# I2C_Keypad.net
KiCad netlist of a schematic drawn in Altium Designer
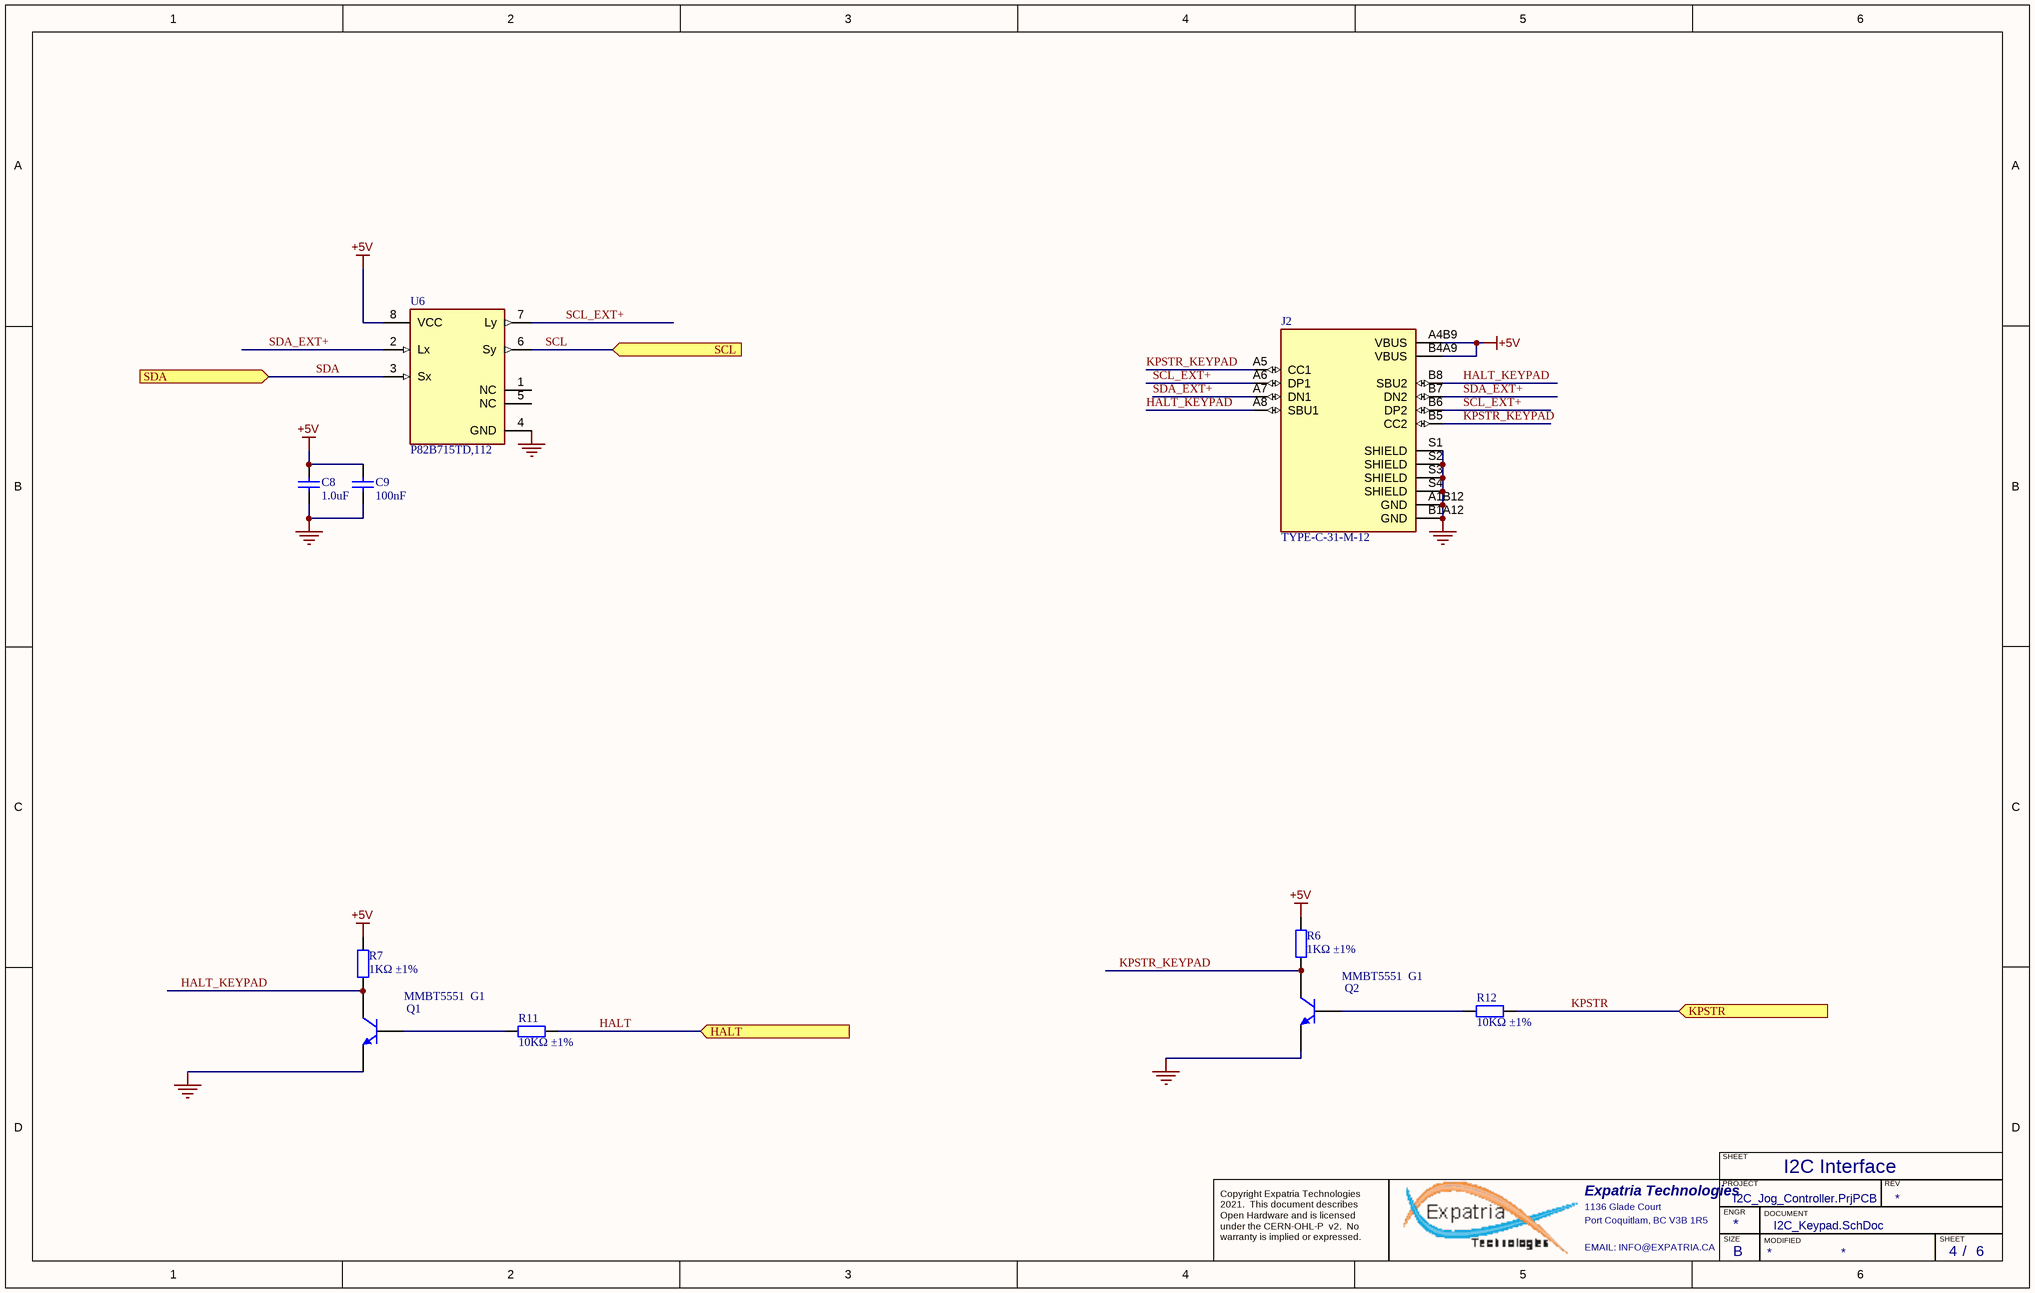
[diagram p0: I2C_Keypad.SchDoc]

(export (version "E")
  (design (tool "Eeschema 10.0.6"))
  (components
    (comp (ref "C8")
      (value "1.0uF")
      (footprint "0402_C")
      (description "Chip capacitor")
      (fields
        (field (name "MANUFACTURER") "Samsung Electro-Mechanics")
        (field (name "PARTNUMBER") "CL05A105KA5NQNC")
      )
      (libsource (lib "Cap") (part "0402 1.0uF (105) 10% 25V"))
    )
    (comp (ref "C9")
      (value "100nF")
      (footprint "0402_C")
      (description "Chip capacitors")
      (fields
        (field (name "MANUFACTURER") "Samsung Electro-Mechanics")
        (field (name "PARTNUMBER") "CL05B104KO5NNNC")
      )
      (libsource (lib "Cap") (part "0402 100nF (104) 10% 16V"))
    )
    (comp (ref "J2")
      (value "TYPE-C-31-M-12")
      (footprint "HRO_TYPE-C-31-M-12")
      (description "USB Connectors 24 Receptacle 1 8.94*7.3mm RoHS")
      (fields (field (name "MF") "HRO Electronics Co., Ltd."))
      (libsource (lib "Universal_CNC_Breakout") (part "TYPE-C-31-M-12"))
    )
    (comp (ref "Q1")
      (value "MMBT5551  G1")
      (footprint "SOT-23(SOT-23-3)")
      (description "三极管")
      (libsource (lib "Transistor_NPN") (part "SOT-23 MMBT5551  G1"))
    )
    (comp (ref "Q2")
      (value "MMBT5551  G1")
      (footprint "SOT-23(SOT-23-3)")
      (description "三极管")
      (libsource (lib "Transistor_NPN") (part "SOT-23 MMBT5551  G1"))
    )
    (comp (ref "R6")
      (value "1KΩ ±1%")
      (footprint "0402_R")
      (description "Chip resistor")
      (fields (field (name "MANUFACTURER") "Uniroyal Elec") (field (name "PARTNUMBER") "0402WGF1001TCE"))
      (libsource (lib "RES") (part "0402 1K (1001) 1%"))
    )
    (comp (ref "R7")
      (value "1KΩ ±1%")
      (footprint "0402_R")
      (description "Chip resistor")
      (fields (field (name "MANUFACTURER") "Uniroyal Elec") (field (name "PARTNUMBER") "0402WGF1001TCE"))
      (libsource (lib "RES") (part "0402 1K (1001) 1%"))
    )
    (comp (ref "R11")
      (value "10KΩ ±1%")
      (footprint "0402_R")
      (description "Chip resistor")
      (fields (field (name "MANUFACTURER") "Uniroyal Elec") (field (name "PARTNUMBER") "0402WGF1002TCE"))
      (libsource (lib "") (part "0402 10K (1002) 1%_1"))
    )
    (comp (ref "R12")
      (value "10KΩ ±1%")
      (footprint "0402_R")
      (description "Chip resistor")
      (fields (field (name "MANUFACTURER") "Uniroyal Elec") (field (name "PARTNUMBER") "0402WGF1002TCE"))
      (libsource (lib "RES") (part "0402 10K (1002) 1%"))
    )
    (comp (ref "U6")
      (value "P82B715TD,112")
      (footprint "FP-SOT96-1-MFG")
      (description "IC REDRIVER I2C 1CH 400KHZ 8SO")
      (fields
        (field (name "MANUFACTURER") "NXP Semicon")
        (field (name "MANUFACTURER_PART_NUMBER") "P82B715TD,118")
      )
      (libsource (lib "Altium Content Vault") (part "feec727f4072afc4f94d4e12e138974"))
    )
  )
  (nets
    (net (code "1") (name "+5V") (class "Default")
      (node (ref "C8") (pin "2") (pinfunction "2_2") (pintype "passive"))
      (node (ref "C9") (pin "2") (pinfunction "2_2") (pintype "passive"))
      (node (ref "J2") (pin "A4B9") (pinfunction "VBUS_A4B9") (pintype "power_in"))
      (node (ref "J2") (pin "B4A9") (pinfunction "VBUS_B4A9") (pintype "power_in"))
      (node (ref "R6") (pin "1") (pinfunction "1_1") (pintype "passive"))
      (node (ref "R7") (pin "1") (pinfunction "1_1") (pintype "passive"))
      (node (ref "U6") (pin "8") (pinfunction "VCC_8") (pintype "power_in"))
    )
    (net (code "2") (name "/HALT") (class "Default")
      (node (ref "R11") (pin "2") (pinfunction "2_2") (pintype "passive"))
    )
    (net (code "3") (name "/HALT_KEYPAD") (class "Default")
      (node (ref "J2") (pin "A8") (pinfunction "SBU1_A8") (pintype "bidirectional"))
      (node (ref "J2") (pin "B8") (pinfunction "SBU2_B8") (pintype "bidirectional"))
      (node (ref "Q1") (pin "3") (pinfunction "C_3") (pintype "passive"))
      (node (ref "R7") (pin "2") (pinfunction "2_2") (pintype "passive"))
    )
    (net (code "4") (name "/KPSTR") (class "Default")
      (node (ref "R12") (pin "1") (pinfunction "1_1") (pintype "passive"))
    )
    (net (code "5") (name "/KPSTR_KEYPAD") (class "Default")
      (node (ref "J2") (pin "A5") (pinfunction "CC1_A5") (pintype "bidirectional"))
      (node (ref "J2") (pin "B5") (pinfunction "CC2_B5") (pintype "bidirectional"))
      (node (ref "Q2") (pin "3") (pinfunction "C_3") (pintype "passive"))
      (node (ref "R6") (pin "2") (pinfunction "2_2") (pintype "passive"))
    )
    (net (code "6") (name "/SCL") (class "Default")
      (node (ref "U6") (pin "6") (pinfunction "Sy_6") (pintype "output"))
    )
    (net (code "7") (name "/SCL_EXT+") (class "Default")
      (node (ref "J2") (pin "A6") (pinfunction "DP1_A6") (pintype "bidirectional"))
      (node (ref "J2") (pin "B6") (pinfunction "DP2_B6") (pintype "bidirectional"))
      (node (ref "U6") (pin "7") (pinfunction "Ly_7") (pintype "output"))
    )
    (net (code "8") (name "/SDA") (class "Default")
      (node (ref "U6") (pin "3") (pinfunction "Sx_3") (pintype "input"))
    )
    (net (code "9") (name "/SDA_EXT+") (class "Default")
      (node (ref "J2") (pin "A7") (pinfunction "DN1_A7") (pintype "bidirectional"))
      (node (ref "J2") (pin "B7") (pinfunction "DN2_B7") (pintype "bidirectional"))
      (node (ref "U6") (pin "2") (pinfunction "Lx_2") (pintype "input"))
    )
    (net (code "10") (name "GND") (class "Default")
      (node (ref "C8") (pin "1") (pinfunction "1_1") (pintype "passive"))
      (node (ref "C9") (pin "1") (pinfunction "1_1") (pintype "passive"))
      (node (ref "J2") (pin "A1B12") (pinfunction "GND_A1B12") (pintype "power_in"))
      (node (ref "J2") (pin "B1A12") (pinfunction "GND_B1A12") (pintype "power_in"))
      (node (ref "J2") (pin "S1") (pinfunction "SHIELD_S1") (pintype "passive"))
      (node (ref "J2") (pin "S2") (pinfunction "SHIELD_S2") (pintype "passive"))
      (node (ref "J2") (pin "S3") (pinfunction "SHIELD_S3") (pintype "passive"))
      (node (ref "J2") (pin "S4") (pinfunction "SHIELD_S4") (pintype "passive"))
      (node (ref "Q1") (pin "2") (pinfunction "E_2") (pintype "passive"))
      (node (ref "Q2") (pin "2") (pinfunction "E_2") (pintype "passive"))
      (node (ref "U6") (pin "4") (pinfunction "GND_4") (pintype "power_in"))
    )
    (net (code "11") (name "Net-(Q1-B)") (class "Default")
      (node (ref "Q1") (pin "1") (pinfunction "B_1") (pintype "passive"))
      (node (ref "R11") (pin "1") (pinfunction "1_1") (pintype "passive"))
    )
    (net (code "12") (name "Net-(Q2-B)") (class "Default")
      (node (ref "Q2") (pin "1") (pinfunction "B_1") (pintype "passive"))
      (node (ref "R12") (pin "2") (pinfunction "2_2") (pintype "passive"))
    )
    (net (code "13") (name "unconnected-(U6-NC-Pad1)") (class "Default")
      (node (ref "U6") (pin "1") (pinfunction "NC_1") (pintype "passive"))
    )
    (net (code "14") (name "unconnected-(U6-NC-Pad5)") (class "Default")
      (node (ref "U6") (pin "5") (pinfunction "NC_5") (pintype "passive"))
    )
  )
)
